# m1k-pot-divider.net
KiCad netlist of a schematic drawn in EAGLE
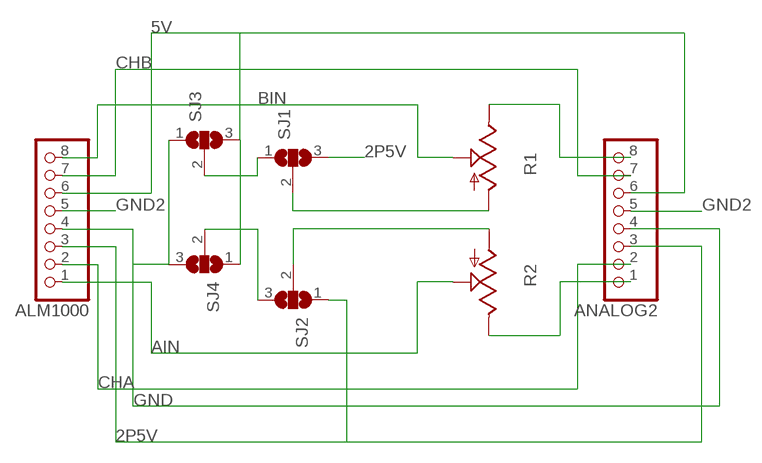
[diagram p0: schematic, sheet 1]

(export (version "E")
  (design (tool "Eeschema 10.0.6"))
  (components
    (comp (ref "ALM1000")
      (value "PINHD-1X8")
      (footprint "eagle-import:1X08")
      (libsource (lib "eagle-import") (part "PINHD-1X8"))
    )
    (comp (ref "ANALOG2")
      (value "PINHD-1X8")
      (footprint "eagle-import:1X08")
      (libsource (lib "eagle-import") (part "PINHD-1X8"))
    )
    (comp (ref "R1")
      (value "TRIM_US-S64W")
      (footprint "eagle-import:S64W")
      (libsource (lib "eagle-import") (part "TRIM_US-S64W"))
    )
    (comp (ref "R2")
      (value "TRIM_US-S64W")
      (footprint "eagle-import:S64W")
      (libsource (lib "eagle-import") (part "TRIM_US-S64W"))
    )
    (comp (ref "SJ1")
      (value "SJ2W")
      (footprint "eagle-import:SJ_2")
      (libsource (lib "eagle-import") (part "SJ2W"))
    )
    (comp (ref "SJ2")
      (value "SJ2W")
      (footprint "eagle-import:SJ_2")
      (libsource (lib "eagle-import") (part "SJ2W"))
    )
    (comp (ref "SJ3")
      (value "SJ2W")
      (footprint "eagle-import:SJ_2")
      (libsource (lib "eagle-import") (part "SJ2W"))
    )
    (comp (ref "SJ4")
      (value "SJ2W")
      (footprint "eagle-import:SJ_2")
      (libsource (lib "eagle-import") (part "SJ2W"))
    )
  )
  (nets
    (net (code "1") (name "/2P5V") (class "Default")
      (node (ref "ALM1000") (pin "3") (pinfunction "3_3") (pintype "passive"))
      (node (ref "ANALOG2") (pin "3") (pinfunction "3_3") (pintype "passive"))
      (node (ref "SJ1") (pin "3") (pinfunction "3_3") (pintype "passive"))
      (node (ref "SJ2") (pin "1") (pinfunction "1_1") (pintype "passive"))
    )
    (net (code "2") (name "/5V") (class "Default")
      (node (ref "ALM1000") (pin "6") (pinfunction "6_6") (pintype "passive"))
      (node (ref "ANALOG2") (pin "6") (pinfunction "6_6") (pintype "passive"))
      (node (ref "SJ3") (pin "3") (pinfunction "3_3") (pintype "passive"))
      (node (ref "SJ4") (pin "1") (pinfunction "1_1") (pintype "passive"))
    )
    (net (code "3") (name "/AIN") (class "Default")
      (node (ref "ALM1000") (pin "1") (pinfunction "1_1") (pintype "passive"))
      (node (ref "R2") (pin "S") (pinfunction "S_S") (pintype "passive"))
    )
    (net (code "4") (name "/BIN") (class "Default")
      (node (ref "ALM1000") (pin "8") (pinfunction "8_8") (pintype "passive"))
      (node (ref "R1") (pin "S") (pinfunction "S_S") (pintype "passive"))
    )
    (net (code "5") (name "/CHA") (class "Default")
      (node (ref "ALM1000") (pin "2") (pinfunction "2_2") (pintype "passive"))
      (node (ref "ANALOG2") (pin "2") (pinfunction "2_2") (pintype "passive"))
    )
    (net (code "6") (name "/CHB") (class "Default")
      (node (ref "ALM1000") (pin "7") (pinfunction "7_7") (pintype "passive"))
      (node (ref "ANALOG2") (pin "7") (pinfunction "7_7") (pintype "passive"))
    )
    (net (code "7") (name "/GND") (class "Default")
      (node (ref "ALM1000") (pin "4") (pinfunction "4_4") (pintype "passive"))
      (node (ref "ANALOG2") (pin "4") (pinfunction "4_4") (pintype "passive"))
      (node (ref "SJ3") (pin "1") (pinfunction "1_1") (pintype "passive"))
      (node (ref "SJ4") (pin "3") (pinfunction "3_3") (pintype "passive"))
    )
    (net (code "8") (name "/GND2") (class "Default")
      (node (ref "ALM1000") (pin "5") (pinfunction "5_5") (pintype "passive"))
      (node (ref "ANALOG2") (pin "5") (pinfunction "5_5") (pintype "passive"))
    )
    (net (code "9") (name "Net-(ANALOG2-Pad1)") (class "Default")
      (node (ref "ANALOG2") (pin "1") (pinfunction "1_1") (pintype "passive"))
      (node (ref "R2") (pin "E") (pinfunction "E_E") (pintype "passive"))
    )
    (net (code "10") (name "Net-(ANALOG2-Pad8)") (class "Default")
      (node (ref "ANALOG2") (pin "8") (pinfunction "8_8") (pintype "passive"))
      (node (ref "R1") (pin "E") (pinfunction "E_E") (pintype "passive"))
    )
    (net (code "11") (name "Net-(R1-PadA)") (class "Default")
      (node (ref "R1") (pin "A") (pinfunction "A_A") (pintype "passive"))
      (node (ref "SJ1") (pin "2") (pinfunction "2_2") (pintype "passive"))
    )
    (net (code "12") (name "Net-(R2-PadA)") (class "Default")
      (node (ref "R2") (pin "A") (pinfunction "A_A") (pintype "passive"))
      (node (ref "SJ2") (pin "2") (pinfunction "2_2") (pintype "passive"))
    )
    (net (code "13") (name "Net-(SJ1-Pad1)") (class "Default")
      (node (ref "SJ1") (pin "1") (pinfunction "1_1") (pintype "passive"))
      (node (ref "SJ3") (pin "2") (pinfunction "2_2") (pintype "passive"))
    )
    (net (code "14") (name "Net-(SJ2-Pad3)") (class "Default")
      (node (ref "SJ2") (pin "3") (pinfunction "3_3") (pintype "passive"))
      (node (ref "SJ4") (pin "2") (pinfunction "2_2") (pintype "passive"))
    )
  )
)
